# LED_12T-V1_2.net
KiCad netlist of a schematic drawn in Altium Designer
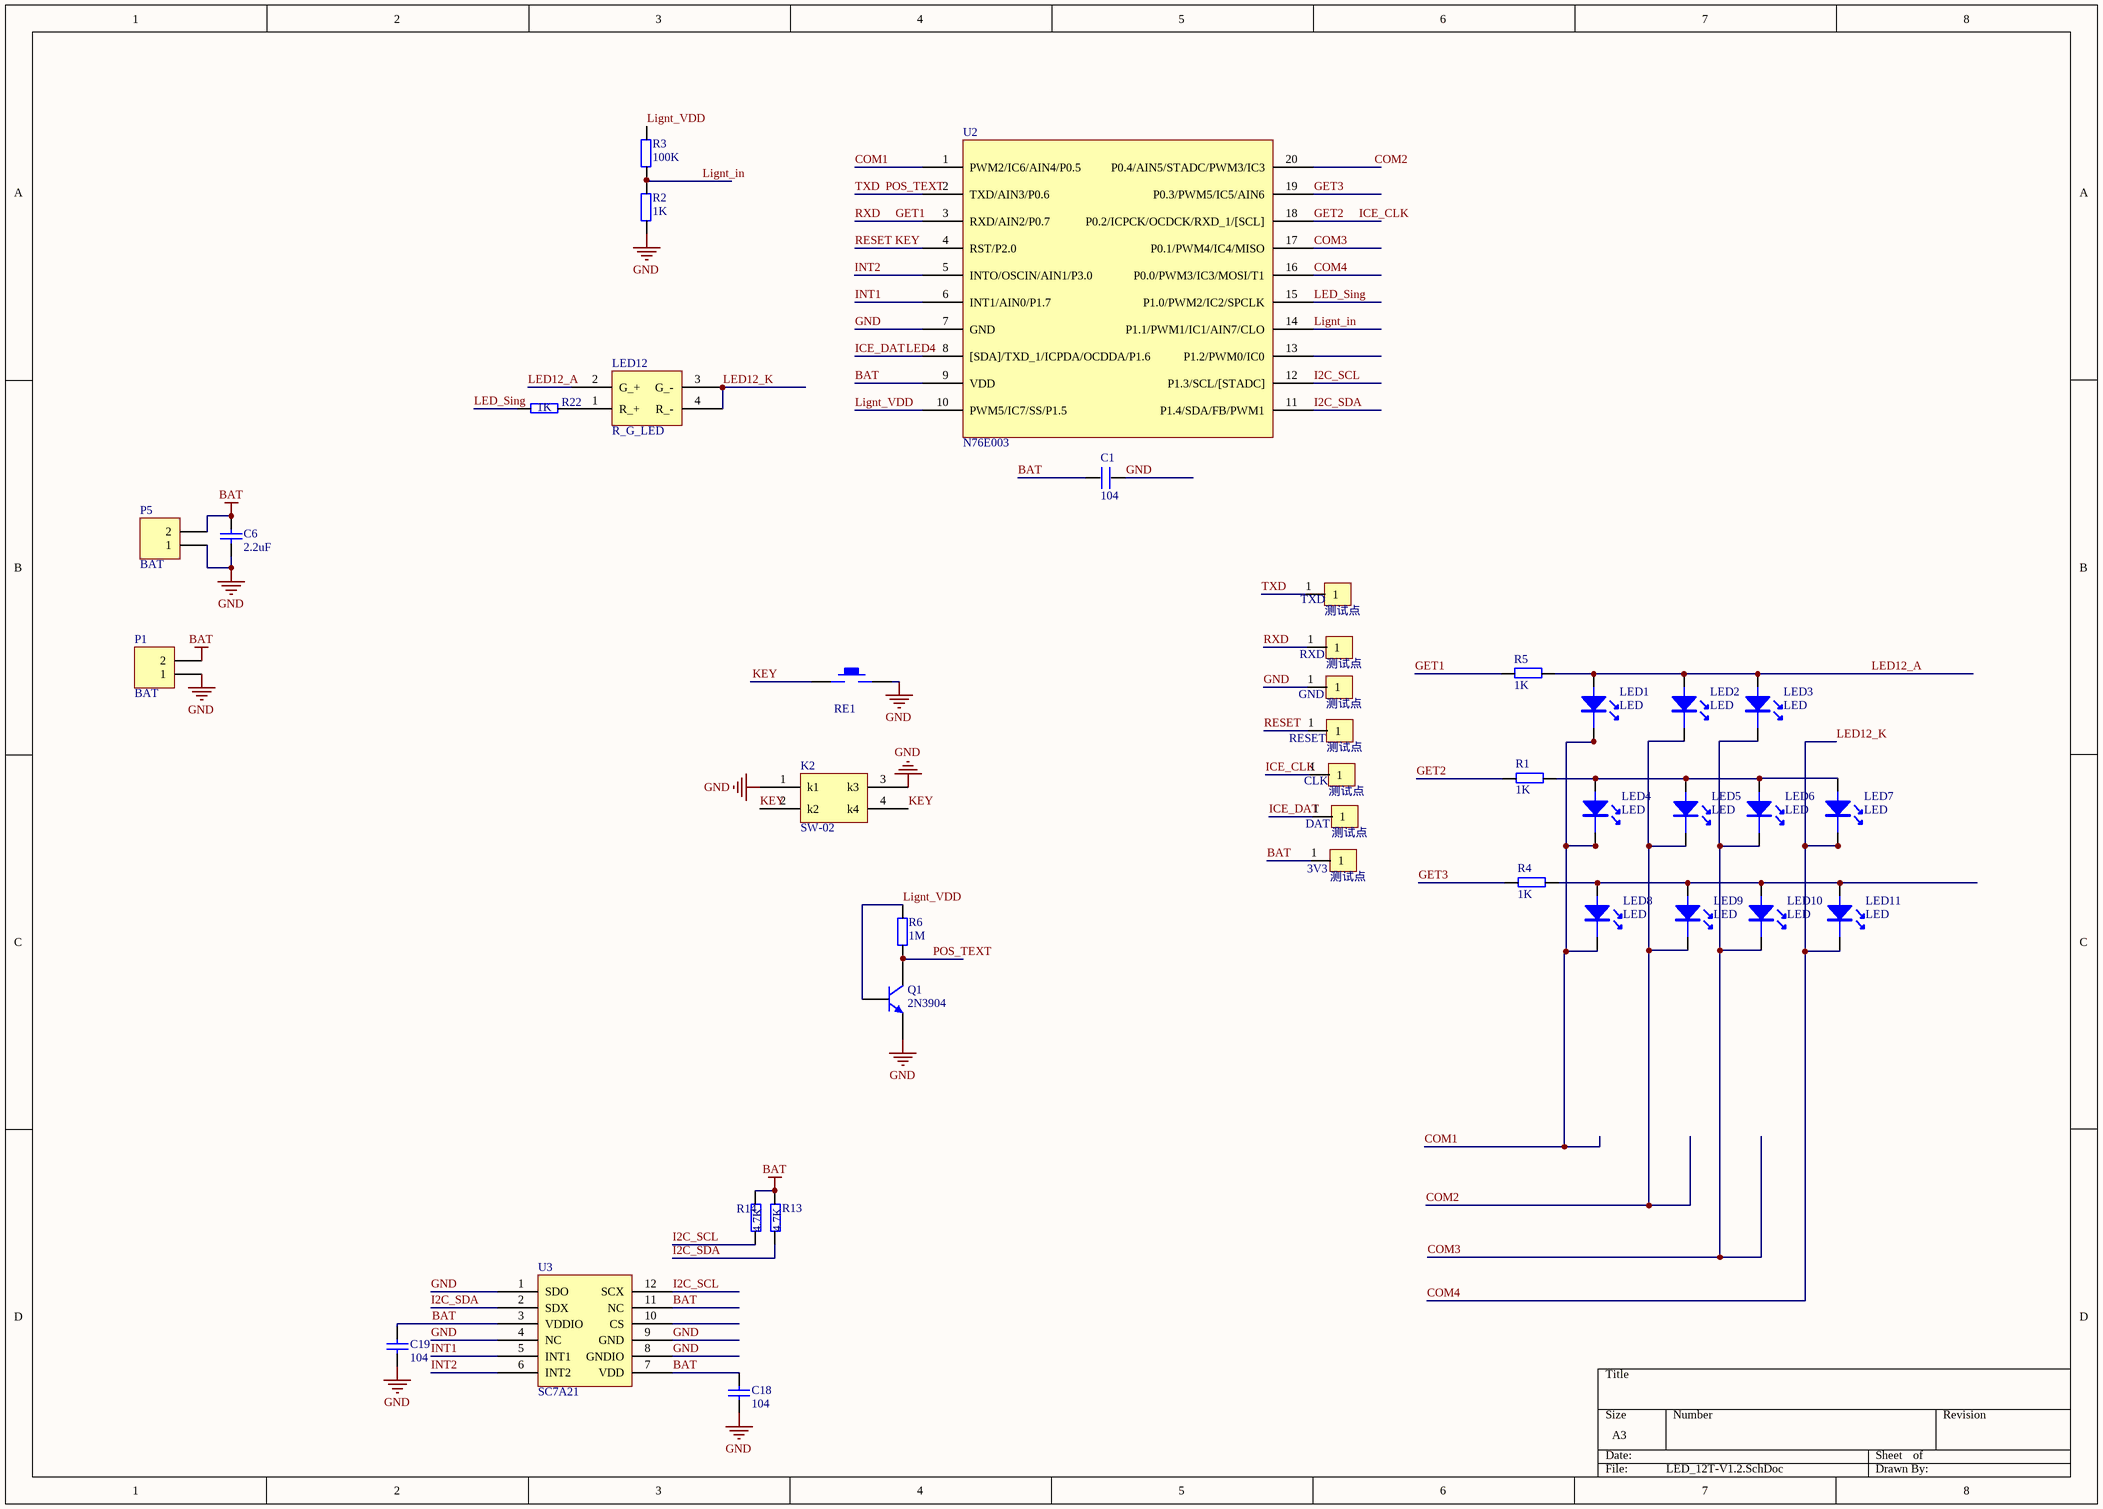
[diagram p0: LED_12T-V1.2.SchDoc]

(export (version "E")
  (design (tool "Eeschema 10.0.6"))
  (components
    (comp (ref "3V3") (value "测试点") (footprint "测试点") (libsource (lib "元件") (part "测试点")))
    (comp (ref "C1") (value "104") (footprint "0603P") (libsource (lib "3.5TFTLCD封装库") (part "C")))
    (comp (ref "C6")
      (value "2.2uF")
      (footprint "0603_C")
      (description "Capacitor")
      (fields (field (name "PUBLISHER") "Altium Limited"))
      (libsource (lib "Miscellaneous Devices") (part "Cap"))
    )
    (comp (ref "C18")
      (value "104")
      (footprint "0402_C")
      (description "Capacitor")
      (fields (field (name "PUBLISHER") "Altium Limited"))
      (libsource (lib "Miscellaneous Devices") (part "Cap"))
    )
    (comp (ref "C19")
      (value "104")
      (footprint "0402_C")
      (description "Capacitor")
      (fields (field (name "PUBLISHER") "Altium Limited"))
      (libsource (lib "Miscellaneous Devices") (part "Cap"))
    )
    (comp (ref "CLK") (value "测试点") (footprint "测试点") (libsource (lib "元件") (part "测试点")))
    (comp (ref "DAT") (value "测试点") (footprint "测试点") (libsource (lib "元件") (part "测试点")))
    (comp (ref "GND") (value "测试点") (footprint "测试点") (libsource (lib "元件") (part "测试点")))
    (comp (ref "K2") (value "SW-02") (footprint "四向滚珠开关") (libsource (lib "元件") (part "SW-02")))
    (comp (ref "LED1") (value "LED") (footprint "0402_LED") (libsource (lib "*") (part "LED")))
    (comp (ref "LED2") (value "LED") (footprint "0402_LED") (libsource (lib "*") (part "LED")))
    (comp (ref "LED3") (value "LED") (footprint "0402_LED") (libsource (lib "*") (part "LED")))
    (comp (ref "LED4") (value "LED") (footprint "0402_LED") (libsource (lib "*") (part "LED")))
    (comp (ref "LED5") (value "LED") (footprint "0402_LED") (libsource (lib "*") (part "LED")))
    (comp (ref "LED6") (value "LED") (footprint "0402_LED") (libsource (lib "*") (part "LED")))
    (comp (ref "LED7") (value "LED") (footprint "0402_LED") (libsource (lib "*") (part "LED")))
    (comp (ref "LED8") (value "LED") (footprint "0402_LED") (libsource (lib "*") (part "LED")))
    (comp (ref "LED9") (value "LED") (footprint "0402_LED") (libsource (lib "*") (part "LED")))
    (comp (ref "LED10") (value "LED") (footprint "0402_LED") (libsource (lib "*") (part "LED")))
    (comp (ref "LED11") (value "LED") (footprint "0402_LED") (libsource (lib "*") (part "LED")))
    (comp (ref "LED12") (value "R_G_LED") (footprint "0603_R_G_LED") (libsource (lib "元件") (part "R_G_LED")))
    (comp (ref "P1")
      (value "BAT")
      (footprint "SH1.0-2P")
      (description "Header, 2-Pin")
      (fields (field (name "PUBLISHER") "Altium Limited"))
      (libsource (lib "Miscellaneous Connectors") (part "Header 2"))
    )
    (comp (ref "P5")
      (value "BAT")
      (footprint "CR2450")
      (description "Header, 2-Pin")
      (fields (field (name "PUBLISHER") "Altium Limited"))
      (libsource (lib "Miscellaneous Connectors") (part "Header 2"))
    )
    (comp (ref "Q1")
      (value "2N3904")
      (footprint "SOT-23")
      (description "NPN General Purpose Amplifier")
      (fields (field (name "PUBLISHER") "Altium Limited"))
      (libsource (lib "Miscellaneous Devices") (part "2N3904"))
    )
    (comp (ref "R1")
      (value "1K")
      (footprint "自画库1:0402_R")
      (libsource (lib "Explorer STM32F407封装库") (part "R"))
    )
    (comp (ref "R2")
      (value "1K")
      (footprint "自画库1:0603_R")
      (libsource (lib "Explorer STM32F407封装库") (part "R"))
    )
    (comp (ref "R3")
      (value "100K")
      (footprint "自画库1:0402_R")
      (libsource (lib "Explorer STM32F407封装库") (part "R"))
    )
    (comp (ref "R4")
      (value "1K")
      (footprint "自画库1:0402_R")
      (libsource (lib "Explorer STM32F407封装库") (part "R"))
    )
    (comp (ref "R5")
      (value "1K")
      (footprint "自画库1:0402_R")
      (libsource (lib "Explorer STM32F407封装库") (part "R"))
    )
    (comp (ref "R6")
      (value "1M")
      (footprint "自画库1:0402_R")
      (libsource (lib "Explorer STM32F407封装库") (part "R"))
    )
    (comp (ref "R13")
      (value "4.7K")
      (footprint "自画库1:0402_R")
      (libsource (lib "Explorer STM32F407封装库") (part "R"))
    )
    (comp (ref "R14")
      (value "4.7K")
      (footprint "自画库1:0402_R")
      (libsource (lib "Explorer STM32F407封装库") (part "R"))
    )
    (comp (ref "R22")
      (value "1K")
      (footprint "自画库1:0402_R")
      (libsource (lib "Explorer STM32F407封装库") (part "R"))
    )
    (comp (ref "RE1")
      (value "KEY_M")
      (footprint "滚珠开关12*3.6")
      (libsource (lib "Explorer STM32F407封装库") (part "KEY_M"))
    )
    (comp (ref "RESET") (value "测试点") (footprint "测试点") (libsource (lib "元件") (part "测试点")))
    (comp (ref "RXD") (value "测试点") (footprint "测试点") (libsource (lib "元件") (part "测试点")))
    (comp (ref "TXD") (value "测试点") (footprint "测试点") (libsource (lib "元件") (part "测试点")))
    (comp (ref "U2") (value "N76E003") (footprint "STSOP20") (libsource (lib "元件") (part "N76E003")))
    (comp (ref "U3") (value "SC7A21") (footprint "自画库1:LGA-12-2*2*1") (libsource (lib "元件") (part "SC7A21")))
  )
  (nets
    (net (code "1") (name "/COM1") (class "Default")
      (node (ref "LED1") (pin "2") (pinfunction "K_2") (pintype "passive"))
      (node (ref "LED4") (pin "2") (pinfunction "K_2") (pintype "passive"))
      (node (ref "LED8") (pin "2") (pinfunction "K_2") (pintype "passive"))
      (node (ref "U2") (pin "1") (pinfunction "PWM2/IC6/AIN4/P0.5_1") (pintype "passive"))
    )
    (net (code "2") (name "/COM2") (class "Default")
      (node (ref "LED2") (pin "2") (pinfunction "K_2") (pintype "passive"))
      (node (ref "LED5") (pin "2") (pinfunction "K_2") (pintype "passive"))
      (node (ref "LED9") (pin "2") (pinfunction "K_2") (pintype "passive"))
      (node (ref "U2") (pin "20") (pinfunction "P0.4/AIN5/STADC/PWM3/IC3_20") (pintype "passive"))
    )
    (net (code "3") (name "/COM3") (class "Default")
      (node (ref "LED10") (pin "2") (pinfunction "K_2") (pintype "passive"))
      (node (ref "LED3") (pin "2") (pinfunction "K_2") (pintype "passive"))
      (node (ref "LED6") (pin "2") (pinfunction "K_2") (pintype "passive"))
      (node (ref "U2") (pin "17") (pinfunction "P0.1/PWM4/IC4/MISO_17") (pintype "passive"))
    )
    (net (code "4") (name "/COM4") (class "Default")
      (node (ref "LED11") (pin "2") (pinfunction "K_2") (pintype "passive"))
      (node (ref "LED12") (pin "3") (pinfunction "G_-_3") (pintype "passive"))
      (node (ref "LED12") (pin "4") (pinfunction "R_-_4") (pintype "passive"))
      (node (ref "LED7") (pin "2") (pinfunction "K_2") (pintype "passive"))
      (node (ref "U2") (pin "16") (pinfunction "P0.0/PWM3/IC3/MOSI/T1_16") (pintype "passive"))
    )
    (net (code "5") (name "/GET1") (class "Default")
      (node (ref "R5") (pin "2") (pintype "passive"))
      (node (ref "RXD") (pin "1") (pinfunction "1_1") (pintype "passive"))
      (node (ref "U2") (pin "3") (pinfunction "RXD/AIN2/P0.7_3") (pintype "passive"))
    )
    (net (code "6") (name "/GET2") (class "Default")
      (node (ref "CLK") (pin "1") (pinfunction "1_1") (pintype "passive"))
      (node (ref "R1") (pin "2") (pintype "passive"))
      (node (ref "U2") (pin "18") (pinfunction "P0.2/ICPCK/OCDCK/RXD_1/[SCL]_18") (pintype "passive"))
    )
    (net (code "7") (name "/GET3") (class "Default")
      (node (ref "R4") (pin "2") (pintype "passive"))
      (node (ref "U2") (pin "19") (pinfunction "P0.3/PWM5/IC5/AIN6_19") (pintype "passive"))
    )
    (net (code "8") (name "/I2C_SCL") (class "Default")
      (node (ref "R14") (pin "1") (pintype "passive"))
      (node (ref "U2") (pin "12") (pinfunction "P1.3/SCL/[STADC]_12") (pintype "passive"))
      (node (ref "U3") (pin "12") (pinfunction "SCX_12") (pintype "passive"))
    )
    (net (code "9") (name "/I2C_SDA") (class "Default")
      (node (ref "R13") (pin "1") (pintype "passive"))
      (node (ref "U2") (pin "11") (pinfunction "P1.4/SDA/FB/PWM1_11") (pintype "passive"))
      (node (ref "U3") (pin "2") (pinfunction "SDX_2") (pintype "passive"))
    )
    (net (code "10") (name "/ICE_DAT") (class "Default")
      (node (ref "DAT") (pin "1") (pinfunction "1_1") (pintype "passive"))
      (node (ref "U2") (pin "8") (pinfunction "[SDA]/TXD_1/ICPDA/OCDDA/P1.6_8") (pintype "passive"))
    )
    (net (code "11") (name "/INT1") (class "Default")
      (node (ref "U2") (pin "6") (pinfunction "INT1/AIN0/P1.7_6") (pintype "passive"))
      (node (ref "U3") (pin "5") (pinfunction "INT1_5") (pintype "passive"))
    )
    (net (code "12") (name "/INT2") (class "Default")
      (node (ref "U2") (pin "5") (pinfunction "INTO/OSCIN/AIN1/P3.0_5") (pintype "passive"))
      (node (ref "U3") (pin "6") (pinfunction "INT2_6") (pintype "passive"))
    )
    (net (code "13") (name "/KEY") (class "Default")
      (node (ref "K2") (pin "2") (pinfunction "k2_2") (pintype "passive"))
      (node (ref "K2") (pin "4") (pinfunction "k4_4") (pintype "passive"))
      (node (ref "RE1") (pin "1") (pinfunction "1_1") (pintype "passive"))
      (node (ref "RESET") (pin "1") (pinfunction "1_1") (pintype "passive"))
      (node (ref "U2") (pin "4") (pinfunction "RST/P2.0_4") (pintype "passive"))
    )
    (net (code "14") (name "/LED12_A") (class "Default")
      (node (ref "LED1") (pin "1") (pinfunction "A_1") (pintype "passive"))
      (node (ref "LED12") (pin "2") (pinfunction "G_+_2") (pintype "passive"))
      (node (ref "LED2") (pin "1") (pinfunction "A_1") (pintype "passive"))
      (node (ref "LED3") (pin "1") (pinfunction "A_1") (pintype "passive"))
      (node (ref "R5") (pin "1") (pintype "passive"))
    )
    (net (code "15") (name "/LED_Sing") (class "Default")
      (node (ref "R22") (pin "2") (pintype "passive"))
      (node (ref "U2") (pin "15") (pinfunction "P1.0/PWM2/IC2/SPCLK_15") (pintype "passive"))
    )
    (net (code "16") (name "/Lignt_VDD") (class "Default")
      (node (ref "Q1") (pin "2") (pinfunction "B_2") (pintype "passive"))
      (node (ref "R3") (pin "1") (pintype "passive"))
      (node (ref "R6") (pin "1") (pintype "passive"))
      (node (ref "U2") (pin "10") (pinfunction "PWM5/IC7/SS/P1.5_10") (pintype "passive"))
    )
    (net (code "17") (name "/Lignt_in") (class "Default")
      (node (ref "R2") (pin "1") (pintype "passive"))
      (node (ref "R3") (pin "2") (pintype "passive"))
      (node (ref "U2") (pin "14") (pinfunction "P1.1/PWM1/IC1/AIN7/CLO_14") (pintype "passive"))
    )
    (net (code "18") (name "/POS_TEXT") (class "Default")
      (node (ref "Q1") (pin "3") (pinfunction "C_3") (pintype "passive"))
      (node (ref "R6") (pin "2") (pintype "passive"))
      (node (ref "TXD") (pin "1") (pinfunction "1_1") (pintype "passive"))
      (node (ref "U2") (pin "2") (pinfunction "TXD/AIN3/P0.6_2") (pintype "passive"))
    )
    (net (code "19") (name "BAT") (class "Default")
      (node (ref "3V3") (pin "1") (pinfunction "1_1") (pintype "passive"))
      (node (ref "C1") (pin "2") (pintype "passive"))
      (node (ref "C18") (pin "1") (pinfunction "1_1") (pintype "passive"))
      (node (ref "C19") (pin "1") (pinfunction "1_1") (pintype "passive"))
      (node (ref "C6") (pin "2") (pinfunction "2_2") (pintype "passive"))
      (node (ref "P1") (pin "2") (pinfunction "2_2") (pintype "passive"))
      (node (ref "P5") (pin "2") (pinfunction "2_2") (pintype "passive"))
      (node (ref "R13") (pin "2") (pintype "passive"))
      (node (ref "R14") (pin "2") (pintype "passive"))
      (node (ref "U2") (pin "9") (pinfunction "VDD_9") (pintype "passive"))
      (node (ref "U3") (pin "11") (pinfunction "NC_11") (pintype "passive"))
      (node (ref "U3") (pin "3") (pinfunction "VDDIO_3") (pintype "passive"))
      (node (ref "U3") (pin "7") (pinfunction "VDD_7") (pintype "passive"))
    )
    (net (code "20") (name "GND") (class "Default")
      (node (ref "C1") (pin "1") (pintype "passive"))
      (node (ref "C18") (pin "2") (pinfunction "2_2") (pintype "passive"))
      (node (ref "C19") (pin "2") (pinfunction "2_2") (pintype "passive"))
      (node (ref "C6") (pin "1") (pinfunction "1_1") (pintype "passive"))
      (node (ref "GND") (pin "1") (pinfunction "1_1") (pintype "passive"))
      (node (ref "K2") (pin "1") (pinfunction "k1_1") (pintype "passive"))
      (node (ref "K2") (pin "3") (pinfunction "k3_3") (pintype "passive"))
      (node (ref "P1") (pin "1") (pinfunction "1_1") (pintype "passive"))
      (node (ref "P5") (pin "1") (pinfunction "1_1") (pintype "passive"))
      (node (ref "Q1") (pin "1") (pinfunction "E_1") (pintype "passive"))
      (node (ref "R2") (pin "2") (pintype "passive"))
      (node (ref "RE1") (pin "2") (pinfunction "2_2") (pintype "passive"))
      (node (ref "U2") (pin "7") (pinfunction "GND_7") (pintype "passive"))
      (node (ref "U3") (pin "1") (pinfunction "SDO_1") (pintype "passive"))
      (node (ref "U3") (pin "4") (pinfunction "NC_4") (pintype "passive"))
      (node (ref "U3") (pin "8") (pinfunction "GNDIO_8") (pintype "passive"))
      (node (ref "U3") (pin "9") (pinfunction "GND_9") (pintype "passive"))
    )
    (net (code "21") (name "Net-(LED4-A)") (class "Default")
      (node (ref "LED4") (pin "1") (pinfunction "A_1") (pintype "passive"))
      (node (ref "LED5") (pin "1") (pinfunction "A_1") (pintype "passive"))
      (node (ref "LED6") (pin "1") (pinfunction "A_1") (pintype "passive"))
      (node (ref "LED7") (pin "1") (pinfunction "A_1") (pintype "passive"))
      (node (ref "R1") (pin "1") (pintype "passive"))
    )
    (net (code "22") (name "Net-(LED10-A)") (class "Default")
      (node (ref "LED10") (pin "1") (pinfunction "A_1") (pintype "passive"))
      (node (ref "LED11") (pin "1") (pinfunction "A_1") (pintype "passive"))
      (node (ref "LED8") (pin "1") (pinfunction "A_1") (pintype "passive"))
      (node (ref "LED9") (pin "1") (pinfunction "A_1") (pintype "passive"))
      (node (ref "R4") (pin "1") (pintype "passive"))
    )
    (net (code "23") (name "Net-(LED12-R_+)") (class "Default")
      (node (ref "LED12") (pin "1") (pinfunction "R_+_1") (pintype "passive"))
      (node (ref "R22") (pin "1") (pintype "passive"))
    )
    (net (code "24") (name "unconnected-(U2-P1.2{slash}PWM0{slash}IC0-Pad13)") (class "Default")
      (node (ref "U2") (pin "13") (pinfunction "P1.2/PWM0/IC0_13") (pintype "passive"))
    )
    (net (code "25") (name "unconnected-(U3-CS-Pad10)") (class "Default")
      (node (ref "U3") (pin "10") (pinfunction "CS_10") (pintype "passive"))
    )
  )
)
